# Master.net
KiCad netlist of a schematic drawn in EAGLE
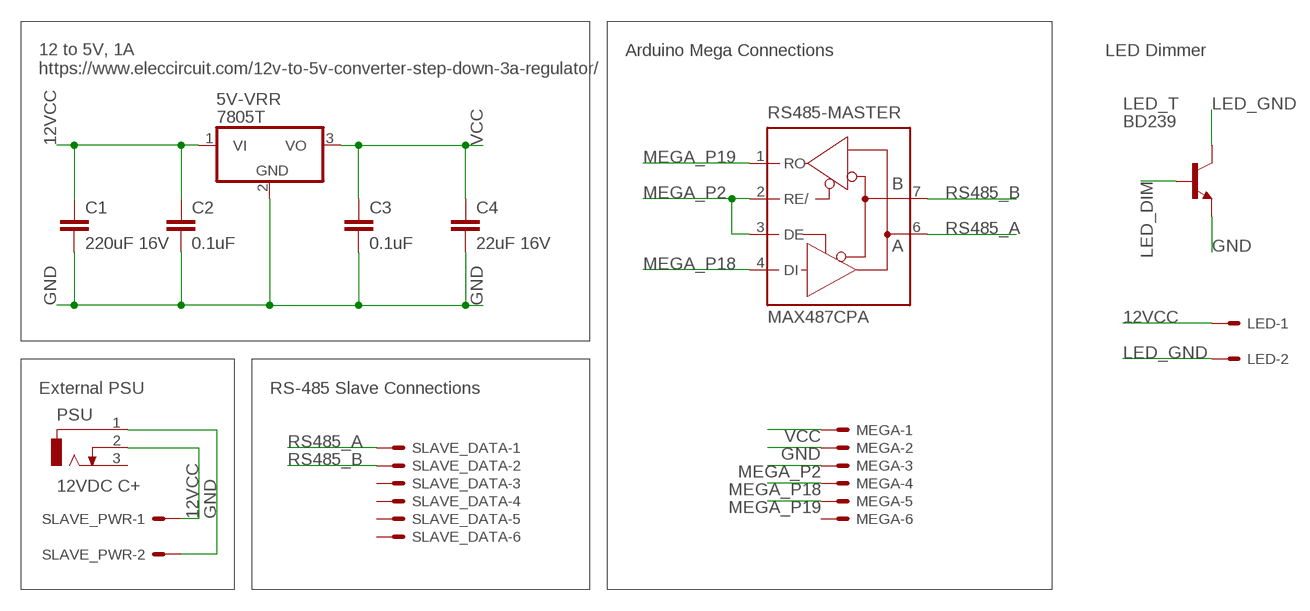
[diagram p0: schematic, sheet 1]

(export (version "E")
  (design (tool "Eeschema 10.0.6"))
  (components
    (comp (ref "5V-VRR")
      (value "7805T")
      (footprint "eagle-import:TO220H")
      (libsource (lib "eagle-import") (part "78T05"))
    )
    (comp (ref "C1")
      (value "220uF 16V")
      (footprint "eagle-import:C025-025X050")
      (libsource (lib "eagle-import") (part "C-EU025-025X050"))
    )
    (comp (ref "C2")
      (value "0.1uF")
      (footprint "eagle-import:C025-025X050")
      (libsource (lib "eagle-import") (part "C-EU025-025X050"))
    )
    (comp (ref "C3")
      (value "0.1uF")
      (footprint "eagle-import:C025-025X050")
      (libsource (lib "eagle-import") (part "C-EU025-025X050"))
    )
    (comp (ref "C4")
      (value "22uF 16V")
      (footprint "eagle-import:C025-025X050")
      (libsource (lib "eagle-import") (part "C-EU025-025X050"))
    )
    (comp (ref "LED")
      (value "KK-156-2")
      (footprint "eagle-import:KK-156-2")
      (fields (field (name "MF") "MOLEX"))
      (libsource (lib "eagle-import") (part "KK-156-2"))
    )
    (comp (ref "LED_T")
      (value "BD239")
      (footprint "eagle-import:TO220")
      (libsource (lib "eagle-import") (part "BD239"))
    )
    (comp (ref "MEGA")
      (value "22-23-2061")
      (footprint "eagle-import:22-23-2061")
      (fields (field (name "MF") "MOLEX"))
      (libsource (lib "eagle-import") (part "22-23-2061"))
    )
    (comp (ref "PSU")
      (value "12VDC C+")
      (footprint "eagle-import:DCJ0202")
      (libsource (lib "eagle-import") (part "DCJ0202"))
    )
    (comp (ref "RS485-MASTER")
      (value "MAX487CPA")
      (footprint "eagle-import:DIL08")
      (libsource (lib "eagle-import") (part "MAX487CPA"))
    )
    (comp (ref "SLAVE_DATA")
      (value "22-23-2061")
      (footprint "eagle-import:22-23-2061")
      (fields (field (name "MF") "MOLEX"))
      (libsource (lib "eagle-import") (part "22-23-2061"))
    )
    (comp (ref "SLAVE_PWR")
      (value "KK-156-2")
      (footprint "eagle-import:KK-156-2")
      (fields (field (name "MF") "MOLEX"))
      (libsource (lib "eagle-import") (part "KK-156-2"))
    )
  )
  (nets
    (net (code "1") (name "/12VCC") (class "Default")
      (node (ref "5V-VRR") (pin "1") (pinfunction "VI_1") (pintype "input"))
      (node (ref "C1") (pin "1") (pinfunction "1_1") (pintype "passive"))
      (node (ref "C2") (pin "1") (pinfunction "1_1") (pintype "passive"))
      (node (ref "LED") (pin "1") (pinfunction "S_1") (pintype "passive"))
      (node (ref "PSU") (pin "2") (pinfunction "2_2") (pintype "passive"))
      (node (ref "SLAVE_PWR") (pin "1") (pinfunction "S_1") (pintype "passive"))
    )
    (net (code "2") (name "/GND") (class "Default")
      (node (ref "5V-VRR") (pin "2") (pinfunction "GND_2") (pintype "passive"))
      (node (ref "C1") (pin "2") (pinfunction "2_2") (pintype "passive"))
      (node (ref "C2") (pin "2") (pinfunction "2_2") (pintype "passive"))
      (node (ref "C3") (pin "2") (pinfunction "2_2") (pintype "passive"))
      (node (ref "C4") (pin "2") (pinfunction "2_2") (pintype "passive"))
      (node (ref "LED_T") (pin "3") (pinfunction "E_3") (pintype "passive"))
      (node (ref "MEGA") (pin "2") (pinfunction "S_2") (pintype "passive"))
      (node (ref "PSU") (pin "1") (pinfunction "1_1") (pintype "passive"))
      (node (ref "SLAVE_PWR") (pin "2") (pinfunction "S_2") (pintype "passive"))
    )
    (net (code "3") (name "/LED_DIM") (class "Default")
      (node (ref "LED_T") (pin "1") (pinfunction "B_1") (pintype "passive"))
    )
    (net (code "4") (name "/LED_GND") (class "Default")
      (node (ref "LED") (pin "2") (pinfunction "S_2") (pintype "passive"))
      (node (ref "LED_T") (pin "2") (pinfunction "C_2") (pintype "passive"))
    )
    (net (code "5") (name "/MEGA_P2") (class "Default")
      (node (ref "MEGA") (pin "3") (pinfunction "S_3") (pintype "passive"))
      (node (ref "RS485-MASTER") (pin "2") (pinfunction "RE/_2") (pintype "input"))
      (node (ref "RS485-MASTER") (pin "3") (pinfunction "DE_3") (pintype "input"))
    )
    (net (code "6") (name "/MEGA_P18") (class "Default")
      (node (ref "MEGA") (pin "4") (pinfunction "S_4") (pintype "passive"))
      (node (ref "RS485-MASTER") (pin "4") (pinfunction "DI_4") (pintype "input"))
    )
    (net (code "7") (name "/MEGA_P19") (class "Default")
      (node (ref "MEGA") (pin "5") (pinfunction "S_5") (pintype "passive"))
      (node (ref "RS485-MASTER") (pin "1") (pinfunction "RO_1") (pintype "output"))
    )
    (net (code "8") (name "/RS485_A") (class "Default")
      (node (ref "RS485-MASTER") (pin "6") (pinfunction "A_6") (pintype "passive"))
      (node (ref "SLAVE_DATA") (pin "1") (pinfunction "S_1") (pintype "passive"))
    )
    (net (code "9") (name "/RS485_B") (class "Default")
      (node (ref "RS485-MASTER") (pin "7") (pinfunction "B_7") (pintype "passive"))
      (node (ref "SLAVE_DATA") (pin "2") (pinfunction "S_2") (pintype "passive"))
    )
    (net (code "10") (name "/VCC") (class "Default")
      (node (ref "5V-VRR") (pin "3") (pinfunction "VO_3") (pintype "passive"))
      (node (ref "C3") (pin "1") (pinfunction "1_1") (pintype "passive"))
      (node (ref "C4") (pin "1") (pinfunction "1_1") (pintype "passive"))
      (node (ref "MEGA") (pin "1") (pinfunction "S_1") (pintype "passive"))
    )
    (net (code "11") (name "unconnected-(MEGAF-S-Pad6)") (class "Default")
      (node (ref "MEGA") (pin "6") (pinfunction "S_6") (pintype "passive"))
    )
    (net (code "12") (name "unconnected-(PSU-Pad3)") (class "Default")
      (node (ref "PSU") (pin "3") (pinfunction "3_3") (pintype "passive"))
    )
    (net (code "13") (name "unconnected-(SLAVE_DATAC-S-Pad3)") (class "Default")
      (node (ref "SLAVE_DATA") (pin "3") (pinfunction "S_3") (pintype "passive"))
    )
    (net (code "14") (name "unconnected-(SLAVE_DATAD-S-Pad4)") (class "Default")
      (node (ref "SLAVE_DATA") (pin "4") (pinfunction "S_4") (pintype "passive"))
    )
    (net (code "15") (name "unconnected-(SLAVE_DATAE-S-Pad5)") (class "Default")
      (node (ref "SLAVE_DATA") (pin "5") (pinfunction "S_5") (pintype "passive"))
    )
    (net (code "16") (name "unconnected-(SLAVE_DATAF-S-Pad6)") (class "Default")
      (node (ref "SLAVE_DATA") (pin "6") (pinfunction "S_6") (pintype "passive"))
    )
  )
)
